# TK101_Tonegenerator_Hovedkort.net
KiCad netlist of a schematic drawn in Altium Designer
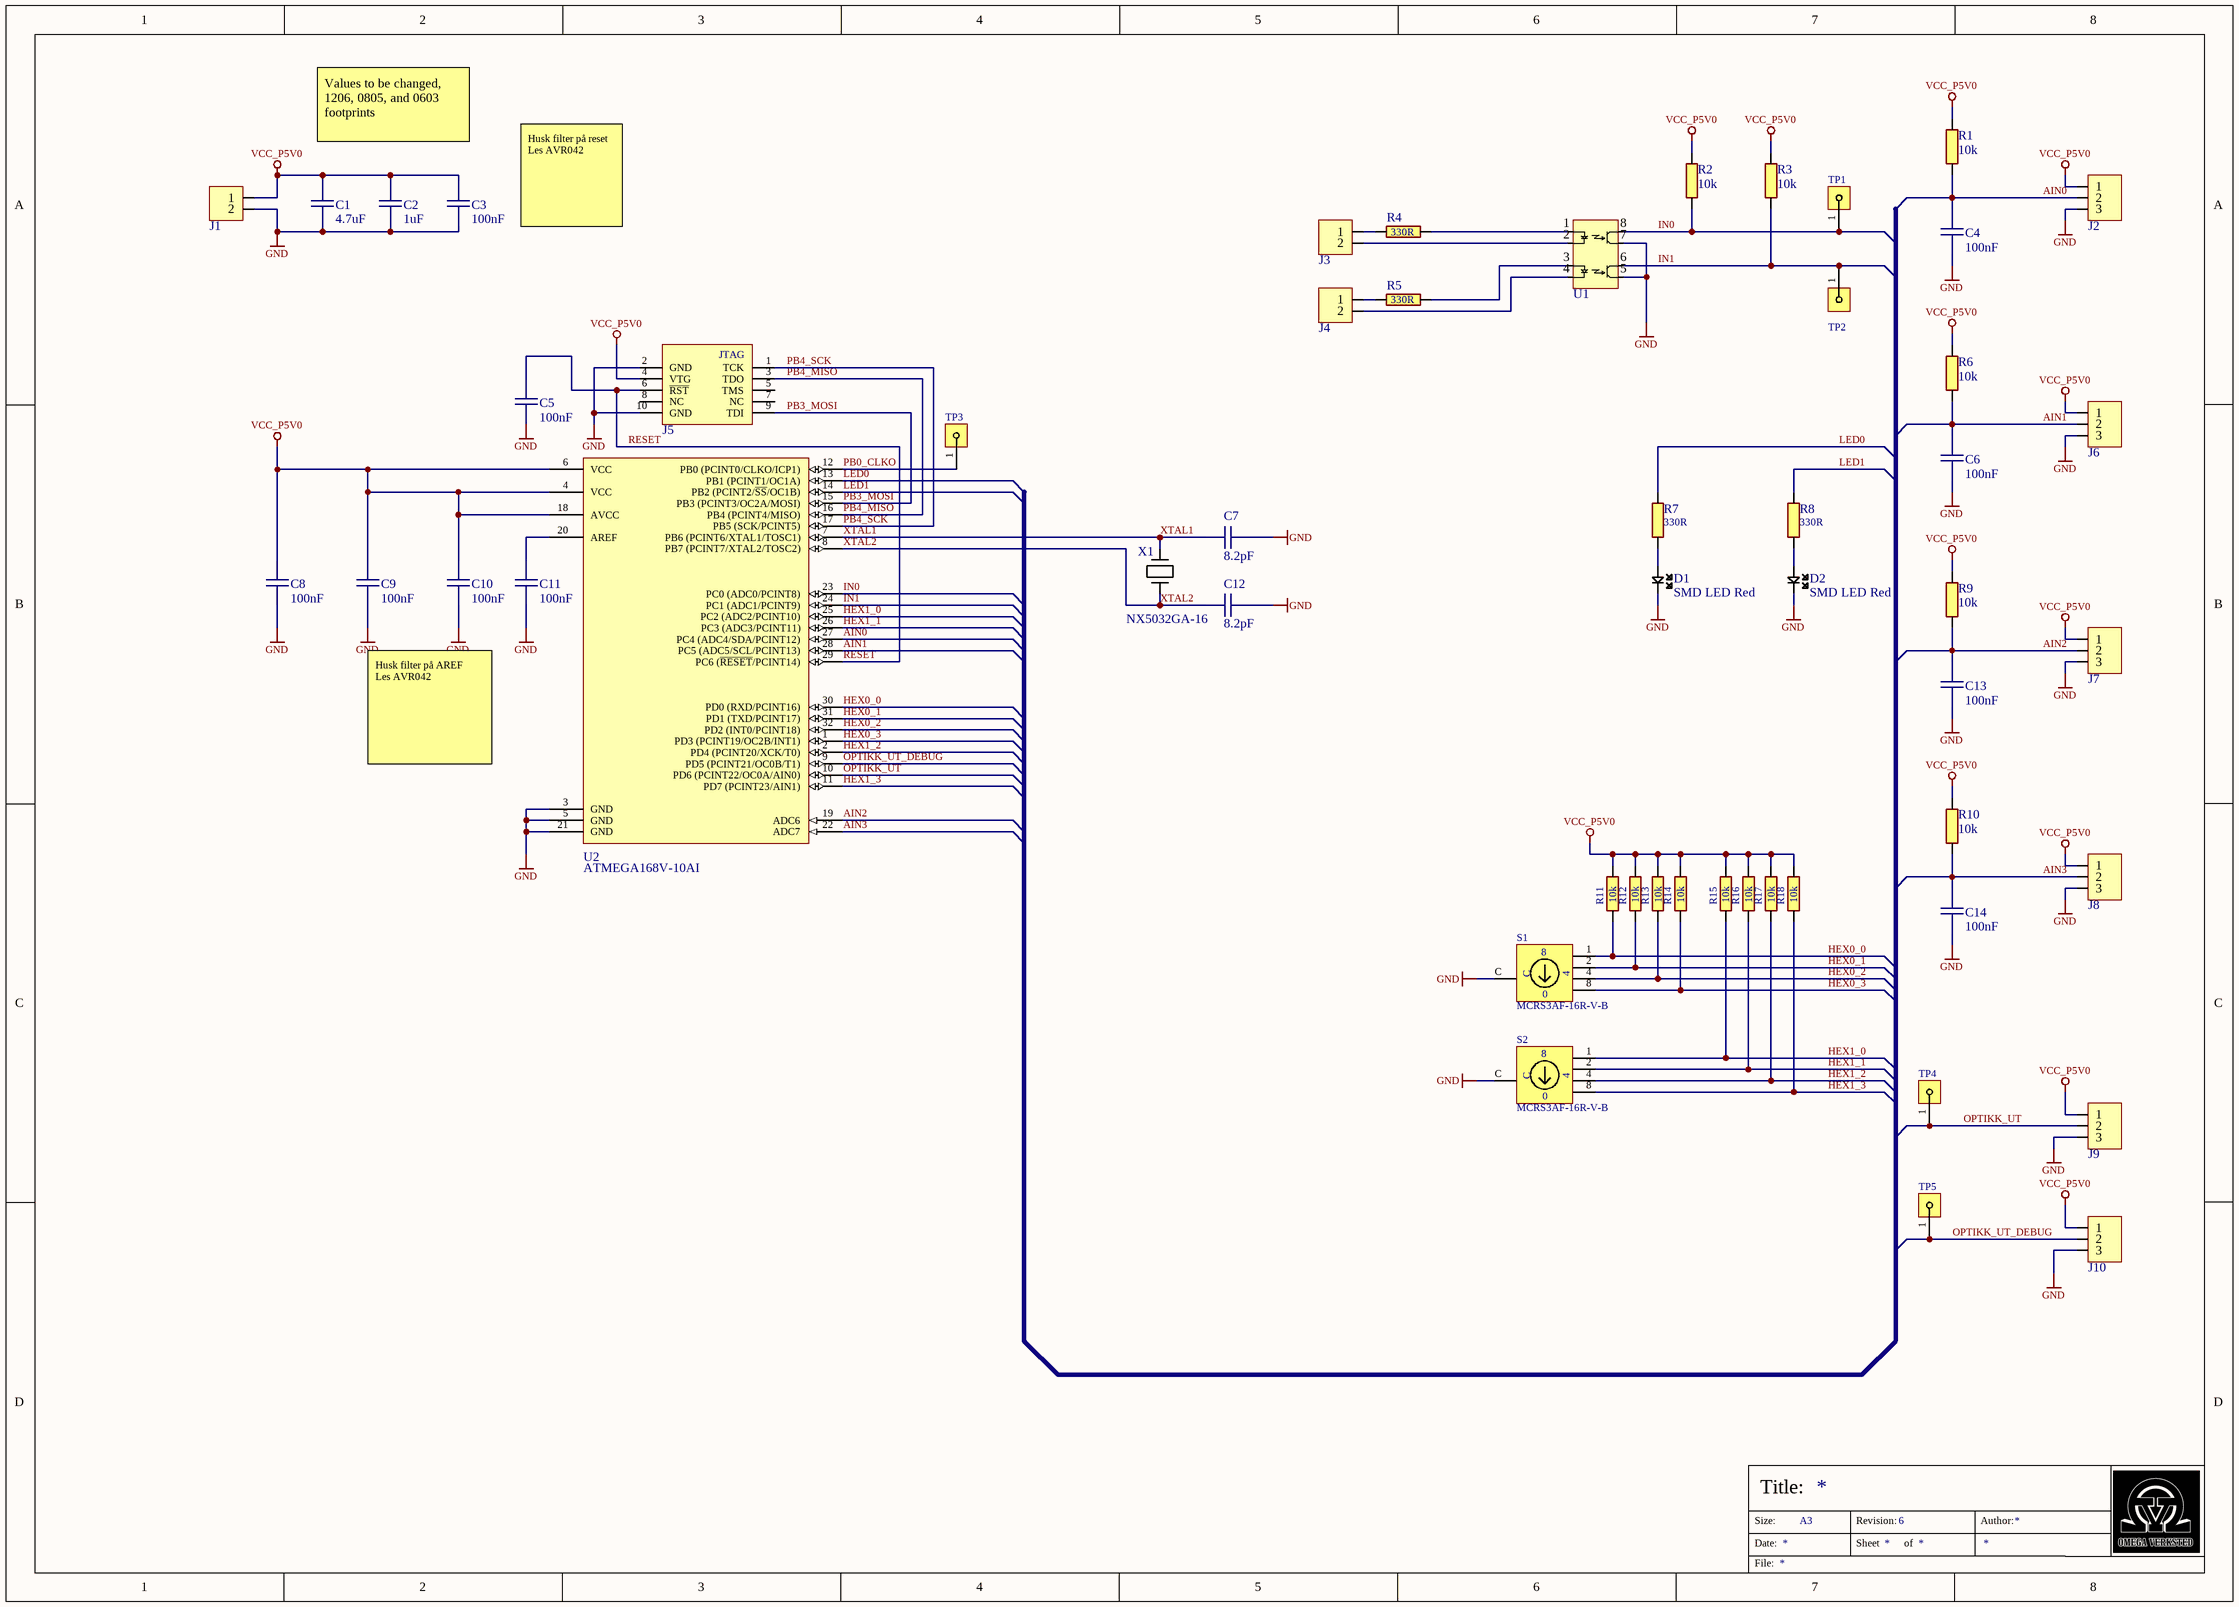
[diagram p0: TK101_Tonegenerator_Hovedkort.SchDoc]

(export (version "E")
  (design (tool "Eeschema 10.0.6"))
  (components
    (comp (ref "C1")
      (value "4.7uF")
      (footprint "CAPC1206(3216)170_N")
      (description "X7R 50V")
      (libsource (lib "OVLib") (part "CAP"))
    )
    (comp (ref "C2")
      (value "1uF")
      (footprint "CAPC0805(2012)100_N")
      (description "X7R 50V 10%")
      (libsource (lib "OVLib") (part "CAP"))
    )
    (comp (ref "C3")
      (value "100nF")
      (footprint "CAPC0603(1608)55_N")
      (description "X7R 50V 5%")
      (libsource (lib "OVLib") (part "CAP"))
    )
    (comp (ref "C4")
      (value "100nF")
      (footprint "CAPC0603(1608)55_N")
      (description "X7R 50V 5%")
      (libsource (lib "OVLib") (part "CAP"))
    )
    (comp (ref "C5")
      (value "100nF")
      (footprint "CAPC0603(1608)55_N")
      (description "X7R 50V 5%")
      (libsource (lib "OVLib") (part "CAP"))
    )
    (comp (ref "C6")
      (value "100nF")
      (footprint "CAPC0603(1608)55_N")
      (description "X7R 50V 5%")
      (libsource (lib "OVLib") (part "CAP"))
    )
    (comp (ref "C7")
      (value "8.2pF")
      (footprint "CAPC0603(1608)55_N")
      (description "NP0 50V 5%")
      (libsource (lib "OVLib") (part "CAP"))
    )
    (comp (ref "C8")
      (value "100nF")
      (footprint "CAPC0603(1608)55_N")
      (description "X7R 50V 5%")
      (libsource (lib "OVLib") (part "CAP"))
    )
    (comp (ref "C9")
      (value "100nF")
      (footprint "CAPC0603(1608)55_N")
      (description "X7R 50V 5%")
      (libsource (lib "OVLib") (part "CAP"))
    )
    (comp (ref "C10")
      (value "100nF")
      (footprint "CAPC0603(1608)55_N")
      (description "X7R 50V 5%")
      (libsource (lib "OVLib") (part "CAP"))
    )
    (comp (ref "C11")
      (value "100nF")
      (footprint "CAPC0603(1608)55_N")
      (description "X7R 50V 5%")
      (libsource (lib "OVLib") (part "CAP"))
    )
    (comp (ref "C12")
      (value "8.2pF")
      (footprint "CAPC0603(1608)55_N")
      (description "NP0 50V 5%")
      (libsource (lib "OVLib") (part "CAP"))
    )
    (comp (ref "C13")
      (value "100nF")
      (footprint "CAPC0603(1608)55_N")
      (description "X7R 50V 5%")
      (libsource (lib "OVLib") (part "CAP"))
    )
    (comp (ref "C14")
      (value "100nF")
      (footprint "CAPC0603(1608)55_N")
      (description "X7R 50V 5%")
      (libsource (lib "OVLib") (part "CAP"))
    )
    (comp (ref "D1")
      (value "SMD LED Red")
      (footprint "I_LEDC0603(1608)_N")
      (libsource (lib "OVLib") (part "LED"))
    )
    (comp (ref "D2")
      (value "SMD LED Red")
      (footprint "I_LEDC0603(1608)_N")
      (libsource (lib "OVLib") (part "LED"))
    )
    (comp (ref "J1")
      (value "JST 2pin")
      (footprint "JST_2P")
      (description "pris pr. stk.")
      (libsource (lib "OVLib") (part "2PConnector"))
    )
    (comp (ref "J2")
      (value "JST 3pin")
      (footprint "JST_3P")
      (description "pris pr. stk.")
      (libsource (lib "OVLib") (part "3PConnector"))
    )
    (comp (ref "J3")
      (value "JST 2pin")
      (footprint "JST_2P")
      (description "pris pr. stk.")
      (libsource (lib "OVLib") (part "2PConnector"))
    )
    (comp (ref "J4")
      (value "JST 2pin")
      (footprint "JST_2P")
      (description "pris pr. stk.")
      (libsource (lib "OVLib") (part "2PConnector"))
    )
    (comp (ref "J5")
      (value "Header SMD 127 2x5")
      (footprint "SMDHDRV10P127_2X5_615X330X560B")
      (description "1,27mm Pitch SMD Header")
      (libsource (lib "OVLib") (part "AVRJTAG"))
    )
    (comp (ref "J6")
      (value "JST 3pin")
      (footprint "JST_3P")
      (description "pris pr. stk.")
      (libsource (lib "OVLib") (part "3PConnector"))
    )
    (comp (ref "J7")
      (value "JST 3pin")
      (footprint "JST_3P")
      (description "pris pr. stk.")
      (libsource (lib "OVLib") (part "3PConnector"))
    )
    (comp (ref "J8")
      (value "JST 3pin")
      (footprint "JST_3P")
      (description "pris pr. stk.")
      (libsource (lib "OVLib") (part "3PConnector"))
    )
    (comp (ref "J9")
      (value "JST 3pin")
      (footprint "JST_3P")
      (description "pris pr. stk.")
      (libsource (lib "OVLib") (part "3PConnector"))
    )
    (comp (ref "J10")
      (value "JST 3pin")
      (footprint "JST_3P")
      (description "pris pr. stk.")
      (libsource (lib "OVLib") (part "3PConnector"))
    )
    (comp (ref "R1")
      (value "10k")
      (footprint "RESC0603(1608)_N")
      (description "0.1W 1% Thick film resistor")
      (libsource (lib "OVLib") (part "Resistor2"))
    )
    (comp (ref "R2")
      (value "10k")
      (footprint "RESC0603(1608)_N")
      (description "0.1W 1% Thick film resistor")
      (libsource (lib "OVLib") (part "Resistor2"))
    )
    (comp (ref "R3")
      (value "10k")
      (footprint "RESC0603(1608)_N")
      (description "0.1W 1% Thick film resistor")
      (libsource (lib "OVLib") (part "Resistor2"))
    )
    (comp (ref "R4")
      (value "330R")
      (footprint "RESC0603(1608)_N")
      (description "0.1W 1% Thick film resistor")
      (libsource (lib "") (part "Resistor2_1"))
    )
    (comp (ref "R5")
      (value "330R")
      (footprint "RESC0603(1608)_N")
      (description "0.1W 1% Thick film resistor")
      (libsource (lib "") (part "Resistor2_1"))
    )
    (comp (ref "R6")
      (value "10k")
      (footprint "RESC0603(1608)_N")
      (description "0.1W 1% Thick film resistor")
      (libsource (lib "OVLib") (part "Resistor2"))
    )
    (comp (ref "R7")
      (value "330R")
      (footprint "RESC0603(1608)_N")
      (description "0.1W 1% Thick film resistor")
      (libsource (lib "OVLib") (part "Resistor2"))
    )
    (comp (ref "R8")
      (value "330R")
      (footprint "RESC0603(1608)_N")
      (description "0.1W 1% Thick film resistor")
      (libsource (lib "OVLib") (part "Resistor2"))
    )
    (comp (ref "R9")
      (value "10k")
      (footprint "RESC0603(1608)_N")
      (description "0.1W 1% Thick film resistor")
      (libsource (lib "OVLib") (part "Resistor2"))
    )
    (comp (ref "R10")
      (value "10k")
      (footprint "RESC0603(1608)_N")
      (description "0.1W 1% Thick film resistor")
      (libsource (lib "OVLib") (part "Resistor2"))
    )
    (comp (ref "R11")
      (value "10k")
      (footprint "RESC0603(1608)_N")
      (description "0.1W 1% Thick film resistor")
      (libsource (lib "OVLib") (part "Resistor2"))
    )
    (comp (ref "R12")
      (value "10k")
      (footprint "RESC0603(1608)_N")
      (description "0.1W 1% Thick film resistor")
      (libsource (lib "OVLib") (part "Resistor2"))
    )
    (comp (ref "R13")
      (value "10k")
      (footprint "RESC0603(1608)_N")
      (description "0.1W 1% Thick film resistor")
      (libsource (lib "OVLib") (part "Resistor2"))
    )
    (comp (ref "R14")
      (value "10k")
      (footprint "RESC0603(1608)_N")
      (description "0.1W 1% Thick film resistor")
      (libsource (lib "OVLib") (part "Resistor2"))
    )
    (comp (ref "R15")
      (value "10k")
      (footprint "RESC0603(1608)_N")
      (description "0.1W 1% Thick film resistor")
      (libsource (lib "OVLib") (part "Resistor2"))
    )
    (comp (ref "R16")
      (value "10k")
      (footprint "RESC0603(1608)_N")
      (description "0.1W 1% Thick film resistor")
      (libsource (lib "OVLib") (part "Resistor2"))
    )
    (comp (ref "R17")
      (value "10k")
      (footprint "RESC0603(1608)_N")
      (description "0.1W 1% Thick film resistor")
      (libsource (lib "OVLib") (part "Resistor2"))
    )
    (comp (ref "R18")
      (value "10k")
      (footprint "RESC0603(1608)_N")
      (description "0.1W 1% Thick film resistor")
      (libsource (lib "OVLib") (part "Resistor2"))
    )
    (comp (ref "S1")
      (value "MCRS3AF-16R-V-B")
      (footprint "MCRS3AF-16R-V-B")
      (description "Rotary hex switch")
      (libsource (lib "OVLib") (part "Hex_switch"))
    )
    (comp (ref "S2")
      (value "MCRS3AF-16R-V-B")
      (footprint "MCRS3AF-16R-V-B")
      (description "Rotary hex switch")
      (libsource (lib "OVLib") (part "Hex_switch"))
    )
    (comp (ref "TP1")
      (value "Header1x1")
      (footprint "HDRV1W64P254_1X1_254X254X900B")
      (libsource (lib "OVLib") (part "Header1x1"))
    )
    (comp (ref "TP2")
      (value "Header1x1")
      (footprint "HDRV1W64P254_1X1_254X254X900B")
      (libsource (lib "") (part "Header1x1_1"))
    )
    (comp (ref "TP3")
      (value "Header1x1")
      (footprint "HDRV1W64P254_1X1_254X254X900B")
      (libsource (lib "OVLib") (part "Header1x1"))
    )
    (comp (ref "TP4")
      (value "Header1x1")
      (footprint "HDRV1W64P254_1X1_254X254X900B")
      (libsource (lib "OVLib") (part "Header1x1"))
    )
    (comp (ref "TP5")
      (value "Header1x1")
      (footprint "HDRV1W64P254_1X1_254X254X900B")
      (libsource (lib "OVLib") (part "Header1x1"))
    )
    (comp (ref "U1")
      (value "Dual_Optocoupler")
      (footprint "SOIC127P590X363-8N")
      (description "Dual Optocoupler")
      (libsource (lib "OVLib") (part "Dual_Optocoupler"))
    )
    (comp (ref "U2")
      (value "ATMEGA168V-10AI")
      (footprint "TQFP80P900X900X120-32N")
      (libsource (lib "OVLib") (part "ATMEGA168V"))
    )
    (comp (ref "X1")
      (value "NX5032GA-16")
      (footprint "CRYSTAL-ABM7")
      (description "Crystal 16 MHz")
      (libsource (lib "OVLib") (part "GENERIC-CRYSTAL"))
    )
  )
  (nets
    (net (code "1") (name "/AIN0") (class "Default")
      (node (ref "C4") (pin "2") (pinfunction "2_2") (pintype "passive"))
      (node (ref "J2") (pin "2") (pinfunction "2_2") (pintype "passive"))
      (node (ref "R1") (pin "1") (pinfunction "1_1") (pintype "passive"))
      (node (ref "U2") (pin "27") (pinfunction "PC4_(ADC4/SDA/PCINT12)_27") (pintype "bidirectional"))
    )
    (net (code "2") (name "/AIN1") (class "Default")
      (node (ref "C6") (pin "2") (pinfunction "2_2") (pintype "passive"))
      (node (ref "J6") (pin "2") (pinfunction "2_2") (pintype "passive"))
      (node (ref "R6") (pin "1") (pinfunction "1_1") (pintype "passive"))
      (node (ref "U2") (pin "28") (pinfunction "PC5_(ADC5/SCL/PCINT13)_28") (pintype "bidirectional"))
    )
    (net (code "3") (name "/AIN2") (class "Default")
      (node (ref "C13") (pin "2") (pinfunction "2_2") (pintype "passive"))
      (node (ref "J7") (pin "2") (pinfunction "2_2") (pintype "passive"))
      (node (ref "R9") (pin "1") (pinfunction "1_1") (pintype "passive"))
      (node (ref "U2") (pin "19") (pinfunction "ADC6_19") (pintype "input"))
    )
    (net (code "4") (name "/AIN3") (class "Default")
      (node (ref "C14") (pin "2") (pinfunction "2_2") (pintype "passive"))
      (node (ref "J8") (pin "2") (pinfunction "2_2") (pintype "passive"))
      (node (ref "R10") (pin "1") (pinfunction "1_1") (pintype "passive"))
      (node (ref "U2") (pin "22") (pinfunction "ADC7_22") (pintype "input"))
    )
    (net (code "5") (name "/HEX0_0") (class "Default")
      (node (ref "R11") (pin "1") (pinfunction "1_1") (pintype "passive"))
      (node (ref "S1") (pin "1") (pinfunction "1_1") (pintype "passive"))
      (node (ref "U2") (pin "30") (pinfunction "PD0_(RXD/PCINT16)_30") (pintype "bidirectional"))
    )
    (net (code "6") (name "/HEX0_1") (class "Default")
      (node (ref "R12") (pin "1") (pinfunction "1_1") (pintype "passive"))
      (node (ref "S1") (pin "2") (pinfunction "2_2") (pintype "passive"))
      (node (ref "U2") (pin "31") (pinfunction "PD1_(TXD/PCINT17)_31") (pintype "bidirectional"))
    )
    (net (code "7") (name "/HEX0_2") (class "Default")
      (node (ref "R13") (pin "1") (pinfunction "1_1") (pintype "passive"))
      (node (ref "S1") (pin "4") (pinfunction "4_4") (pintype "passive"))
      (node (ref "U2") (pin "32") (pinfunction "PD2_(INT0/PCINT18)_32") (pintype "bidirectional"))
    )
    (net (code "8") (name "/HEX0_3") (class "Default")
      (node (ref "R14") (pin "1") (pinfunction "1_1") (pintype "passive"))
      (node (ref "S1") (pin "8") (pinfunction "8_8") (pintype "passive"))
      (node (ref "U2") (pin "1") (pinfunction "PD3_(PCINT19/OC2B/INT1)_1") (pintype "bidirectional"))
    )
    (net (code "9") (name "/HEX1_0") (class "Default")
      (node (ref "R15") (pin "1") (pinfunction "1_1") (pintype "passive"))
      (node (ref "S2") (pin "1") (pinfunction "1_1") (pintype "passive"))
      (node (ref "U2") (pin "25") (pinfunction "PC2_(ADC2/PCINT10)_25") (pintype "bidirectional"))
    )
    (net (code "10") (name "/HEX1_1") (class "Default")
      (node (ref "R16") (pin "1") (pinfunction "1_1") (pintype "passive"))
      (node (ref "S2") (pin "2") (pinfunction "2_2") (pintype "passive"))
      (node (ref "U2") (pin "26") (pinfunction "PC3_(ADC3/PCINT11)_26") (pintype "bidirectional"))
    )
    (net (code "11") (name "/HEX1_2") (class "Default")
      (node (ref "R17") (pin "1") (pinfunction "1_1") (pintype "passive"))
      (node (ref "S2") (pin "4") (pinfunction "4_4") (pintype "passive"))
      (node (ref "U2") (pin "2") (pinfunction "PD4_(PCINT20/XCK/T0)_2") (pintype "bidirectional"))
    )
    (net (code "12") (name "/HEX1_3") (class "Default")
      (node (ref "R18") (pin "1") (pinfunction "1_1") (pintype "passive"))
      (node (ref "S2") (pin "8") (pinfunction "8_8") (pintype "passive"))
      (node (ref "U2") (pin "11") (pinfunction "PD7_(PCINT23/AIN1)_11") (pintype "bidirectional"))
    )
    (net (code "13") (name "/IN0") (class "Default")
      (node (ref "R2") (pin "1") (pinfunction "1_1") (pintype "passive"))
      (node (ref "TP1") (pin "1") (pinfunction "1_1") (pintype "passive"))
      (node (ref "U1") (pin "8") (pinfunction "8_8") (pintype "passive"))
      (node (ref "U2") (pin "23") (pinfunction "PC0_(ADC0/PCINT8)_23") (pintype "bidirectional"))
    )
    (net (code "14") (name "/IN1") (class "Default")
      (node (ref "R3") (pin "1") (pinfunction "1_1") (pintype "passive"))
      (node (ref "TP2") (pin "1") (pinfunction "1_1") (pintype "passive"))
      (node (ref "U1") (pin "6") (pinfunction "6_6") (pintype "passive"))
      (node (ref "U2") (pin "24") (pinfunction "PC1_(ADC1/PCINT9)_24") (pintype "bidirectional"))
    )
    (net (code "15") (name "/LED0") (class "Default")
      (node (ref "R7") (pin "2") (pinfunction "2_2") (pintype "passive"))
      (node (ref "U2") (pin "13") (pinfunction "PB1_(PCINT1/OC1A)_13") (pintype "bidirectional"))
    )
    (net (code "16") (name "/LED1") (class "Default")
      (node (ref "R8") (pin "2") (pinfunction "2_2") (pintype "passive"))
      (node (ref "U2") (pin "14") (pinfunction "PB2_(PCINT2/~{SS}/OC1B)_14") (pintype "bidirectional"))
    )
    (net (code "17") (name "/OPTIKK_UT") (class "Default")
      (node (ref "J9") (pin "2") (pinfunction "2_2") (pintype "passive"))
      (node (ref "TP4") (pin "1") (pinfunction "1_1") (pintype "passive"))
      (node (ref "U2") (pin "10") (pinfunction "PD6_(PCINT22/OC0A/AIN0)_10") (pintype "bidirectional"))
    )
    (net (code "18") (name "/OPTIKK_UT_DEBUG") (class "Default")
      (node (ref "J10") (pin "2") (pinfunction "2_2") (pintype "passive"))
      (node (ref "TP5") (pin "1") (pinfunction "1_1") (pintype "passive"))
      (node (ref "U2") (pin "9") (pinfunction "PD5_(PCINT21/OC0B/T1)_9") (pintype "bidirectional"))
    )
    (net (code "19") (name "/PB0_CLKO") (class "Default")
      (node (ref "TP3") (pin "1") (pinfunction "1_1") (pintype "passive"))
      (node (ref "U2") (pin "12") (pinfunction "PB0_(PCINT0/CLKO/ICP1)_12") (pintype "bidirectional"))
    )
    (net (code "20") (name "/PB3_MOSI") (class "Default")
      (node (ref "J5") (pin "9") (pinfunction "TDI_9") (pintype "passive"))
      (node (ref "U2") (pin "15") (pinfunction "PB3_(PCINT3/OC2A/MOSI)_15") (pintype "bidirectional"))
    )
    (net (code "21") (name "/PB4_MISO") (class "Default")
      (node (ref "J5") (pin "3") (pinfunction "TDO_3") (pintype "passive"))
      (node (ref "U2") (pin "16") (pinfunction "PB4_(PCINT4/MISO)_16") (pintype "bidirectional"))
    )
    (net (code "22") (name "/PB4_SCK") (class "Default")
      (node (ref "J5") (pin "1") (pinfunction "TCK_1") (pintype "passive"))
      (node (ref "U2") (pin "17") (pinfunction "PB5_(SCK/PCINT5)_17") (pintype "bidirectional"))
    )
    (net (code "23") (name "/RESET") (class "Default")
      (node (ref "C5") (pin "2") (pinfunction "2_2") (pintype "passive"))
      (node (ref "J5") (pin "6") (pinfunction "~{RST}_6") (pintype "passive"))
      (node (ref "U2") (pin "29") (pinfunction "PC6_(~{RESET}/PCINT14)_29") (pintype "bidirectional"))
    )
    (net (code "24") (name "/XTAL1") (class "Default")
      (node (ref "C7") (pin "2") (pinfunction "2_2") (pintype "passive"))
      (node (ref "U2") (pin "7") (pinfunction "PB6_(PCINT6/XTAL1/TOSC1)_7") (pintype "bidirectional"))
      (node (ref "X1") (pin "1") (pintype "passive"))
    )
    (net (code "25") (name "/XTAL2") (class "Default")
      (node (ref "C12") (pin "2") (pinfunction "2_2") (pintype "passive"))
      (node (ref "U2") (pin "8") (pinfunction "PB7_(PCINT7/XTAL2/TOSC2)_8") (pintype "bidirectional"))
      (node (ref "X1") (pin "2") (pintype "passive"))
    )
    (net (code "26") (name "GND") (class "Default")
      (node (ref "C1") (pin "1") (pinfunction "1_1") (pintype "passive"))
      (node (ref "C10") (pin "1") (pinfunction "1_1") (pintype "passive"))
      (node (ref "C11") (pin "1") (pinfunction "1_1") (pintype "passive"))
      (node (ref "C12") (pin "1") (pinfunction "1_1") (pintype "passive"))
      (node (ref "C13") (pin "1") (pinfunction "1_1") (pintype "passive"))
      (node (ref "C14") (pin "1") (pinfunction "1_1") (pintype "passive"))
      (node (ref "C2") (pin "1") (pinfunction "1_1") (pintype "passive"))
      (node (ref "C3") (pin "1") (pinfunction "1_1") (pintype "passive"))
      (node (ref "C4") (pin "1") (pinfunction "1_1") (pintype "passive"))
      (node (ref "C5") (pin "1") (pinfunction "1_1") (pintype "passive"))
      (node (ref "C6") (pin "1") (pinfunction "1_1") (pintype "passive"))
      (node (ref "C7") (pin "1") (pinfunction "1_1") (pintype "passive"))
      (node (ref "C8") (pin "2") (pinfunction "2_2") (pintype "passive"))
      (node (ref "C9") (pin "2") (pinfunction "2_2") (pintype "passive"))
      (node (ref "D1") (pin "2") (pinfunction "2_2") (pintype "passive"))
      (node (ref "D2") (pin "2") (pinfunction "2_2") (pintype "passive"))
      (node (ref "J1") (pin "2") (pinfunction "2_2") (pintype "passive"))
      (node (ref "J10") (pin "3") (pinfunction "3_3") (pintype "passive"))
      (node (ref "J2") (pin "3") (pinfunction "3_3") (pintype "passive"))
      (node (ref "J5") (pin "10") (pinfunction "GND_10") (pintype "passive"))
      (node (ref "J5") (pin "2") (pinfunction "GND_2") (pintype "passive"))
      (node (ref "J6") (pin "3") (pinfunction "3_3") (pintype "passive"))
      (node (ref "J7") (pin "3") (pinfunction "3_3") (pintype "passive"))
      (node (ref "J8") (pin "3") (pinfunction "3_3") (pintype "passive"))
      (node (ref "J9") (pin "3") (pinfunction "3_3") (pintype "passive"))
      (node (ref "S1") (pin "C") (pinfunction "C_C") (pintype "passive"))
      (node (ref "S2") (pin "C") (pinfunction "C_C") (pintype "passive"))
      (node (ref "U1") (pin "5") (pinfunction "5_5") (pintype "passive"))
      (node (ref "U1") (pin "7") (pinfunction "7_7") (pintype "passive"))
      (node (ref "U2") (pin "21") (pinfunction "GND_21") (pintype "power_in"))
      (node (ref "U2") (pin "3") (pinfunction "GND_3") (pintype "power_in"))
      (node (ref "U2") (pin "5") (pinfunction "GND_5") (pintype "power_in"))
    )
    (net (code "27") (name "Net-(D1-Pad1)") (class "Default")
      (node (ref "D1") (pin "1") (pinfunction "1_1") (pintype "passive"))
      (node (ref "R7") (pin "1") (pinfunction "1_1") (pintype "passive"))
    )
    (net (code "28") (name "Net-(D2-Pad1)") (class "Default")
      (node (ref "D2") (pin "1") (pinfunction "1_1") (pintype "passive"))
      (node (ref "R8") (pin "1") (pinfunction "1_1") (pintype "passive"))
    )
    (net (code "29") (name "Net-(J3-Pad1)") (class "Default")
      (node (ref "J3") (pin "1") (pinfunction "1_1") (pintype "passive"))
      (node (ref "R4") (pin "1") (pinfunction "1_1") (pintype "passive"))
    )
    (net (code "30") (name "Net-(J3-Pad2)") (class "Default")
      (node (ref "J3") (pin "2") (pinfunction "2_2") (pintype "passive"))
      (node (ref "U1") (pin "2") (pinfunction "2_2") (pintype "passive"))
    )
    (net (code "31") (name "Net-(J4-Pad1)") (class "Default")
      (node (ref "J4") (pin "1") (pinfunction "1_1") (pintype "passive"))
      (node (ref "R5") (pin "1") (pinfunction "1_1") (pintype "passive"))
    )
    (net (code "32") (name "Net-(J4-Pad2)") (class "Default")
      (node (ref "J4") (pin "2") (pinfunction "2_2") (pintype "passive"))
      (node (ref "U1") (pin "4") (pinfunction "4_4") (pintype "passive"))
    )
    (net (code "33") (name "Net-(R4-Pad2)") (class "Default")
      (node (ref "R4") (pin "2") (pinfunction "2_2") (pintype "passive"))
      (node (ref "U1") (pin "1") (pinfunction "1_1") (pintype "passive"))
    )
    (net (code "34") (name "Net-(R5-Pad2)") (class "Default")
      (node (ref "R5") (pin "2") (pinfunction "2_2") (pintype "passive"))
      (node (ref "U1") (pin "3") (pinfunction "3_3") (pintype "passive"))
    )
    (net (code "35") (name "Net-(U2-AREF)") (class "Default")
      (node (ref "C11") (pin "2") (pinfunction "2_2") (pintype "passive"))
      (node (ref "U2") (pin "20") (pinfunction "AREF_20") (pintype "passive"))
    )
    (net (code "36") (name "VCC_P5V0") (class "Default")
      (node (ref "C1") (pin "2") (pinfunction "2_2") (pintype "passive"))
      (node (ref "C10") (pin "2") (pinfunction "2_2") (pintype "passive"))
      (node (ref "C2") (pin "2") (pinfunction "2_2") (pintype "passive"))
      (node (ref "C3") (pin "2") (pinfunction "2_2") (pintype "passive"))
      (node (ref "C8") (pin "1") (pinfunction "1_1") (pintype "passive"))
      (node (ref "C9") (pin "1") (pinfunction "1_1") (pintype "passive"))
      (node (ref "J1") (pin "1") (pinfunction "1_1") (pintype "passive"))
      (node (ref "J10") (pin "1") (pinfunction "1_1") (pintype "passive"))
      (node (ref "J2") (pin "1") (pinfunction "1_1") (pintype "passive"))
      (node (ref "J5") (pin "4") (pinfunction "VTG_4") (pintype "passive"))
      (node (ref "J6") (pin "1") (pinfunction "1_1") (pintype "passive"))
      (node (ref "J7") (pin "1") (pinfunction "1_1") (pintype "passive"))
      (node (ref "J8") (pin "1") (pinfunction "1_1") (pintype "passive"))
      (node (ref "J9") (pin "1") (pinfunction "1_1") (pintype "passive"))
      (node (ref "R1") (pin "2") (pinfunction "2_2") (pintype "passive"))
      (node (ref "R10") (pin "2") (pinfunction "2_2") (pintype "passive"))
      (node (ref "R11") (pin "2") (pinfunction "2_2") (pintype "passive"))
      (node (ref "R12") (pin "2") (pinfunction "2_2") (pintype "passive"))
      (node (ref "R13") (pin "2") (pinfunction "2_2") (pintype "passive"))
      (node (ref "R14") (pin "2") (pinfunction "2_2") (pintype "passive"))
      (node (ref "R15") (pin "2") (pinfunction "2_2") (pintype "passive"))
      (node (ref "R16") (pin "2") (pinfunction "2_2") (pintype "passive"))
      (node (ref "R17") (pin "2") (pinfunction "2_2") (pintype "passive"))
      (node (ref "R18") (pin "2") (pinfunction "2_2") (pintype "passive"))
      (node (ref "R2") (pin "2") (pinfunction "2_2") (pintype "passive"))
      (node (ref "R3") (pin "2") (pinfunction "2_2") (pintype "passive"))
      (node (ref "R6") (pin "2") (pinfunction "2_2") (pintype "passive"))
      (node (ref "R9") (pin "2") (pinfunction "2_2") (pintype "passive"))
      (node (ref "U2") (pin "18") (pinfunction "AVCC_18") (pintype "power_in"))
      (node (ref "U2") (pin "4") (pinfunction "VCC_4") (pintype "power_in"))
      (node (ref "U2") (pin "6") (pinfunction "VCC_6") (pintype "power_in"))
    )
    (net (code "37") (name "unconnected-(J5-NC-Pad7)") (class "Default")
      (node (ref "J5") (pin "7") (pinfunction "NC_7") (pintype "passive"))
    )
    (net (code "38") (name "unconnected-(J5-NC-Pad8)") (class "Default")
      (node (ref "J5") (pin "8") (pinfunction "NC_8") (pintype "passive"))
    )
    (net (code "39") (name "unconnected-(J5-TMS-Pad5)") (class "Default")
      (node (ref "J5") (pin "5") (pinfunction "TMS_5") (pintype "passive"))
    )
  )
)
